# ONOFRE_ESTORES_COVERS_R1_1.net
KiCad netlist of a schematic drawn in EAGLE
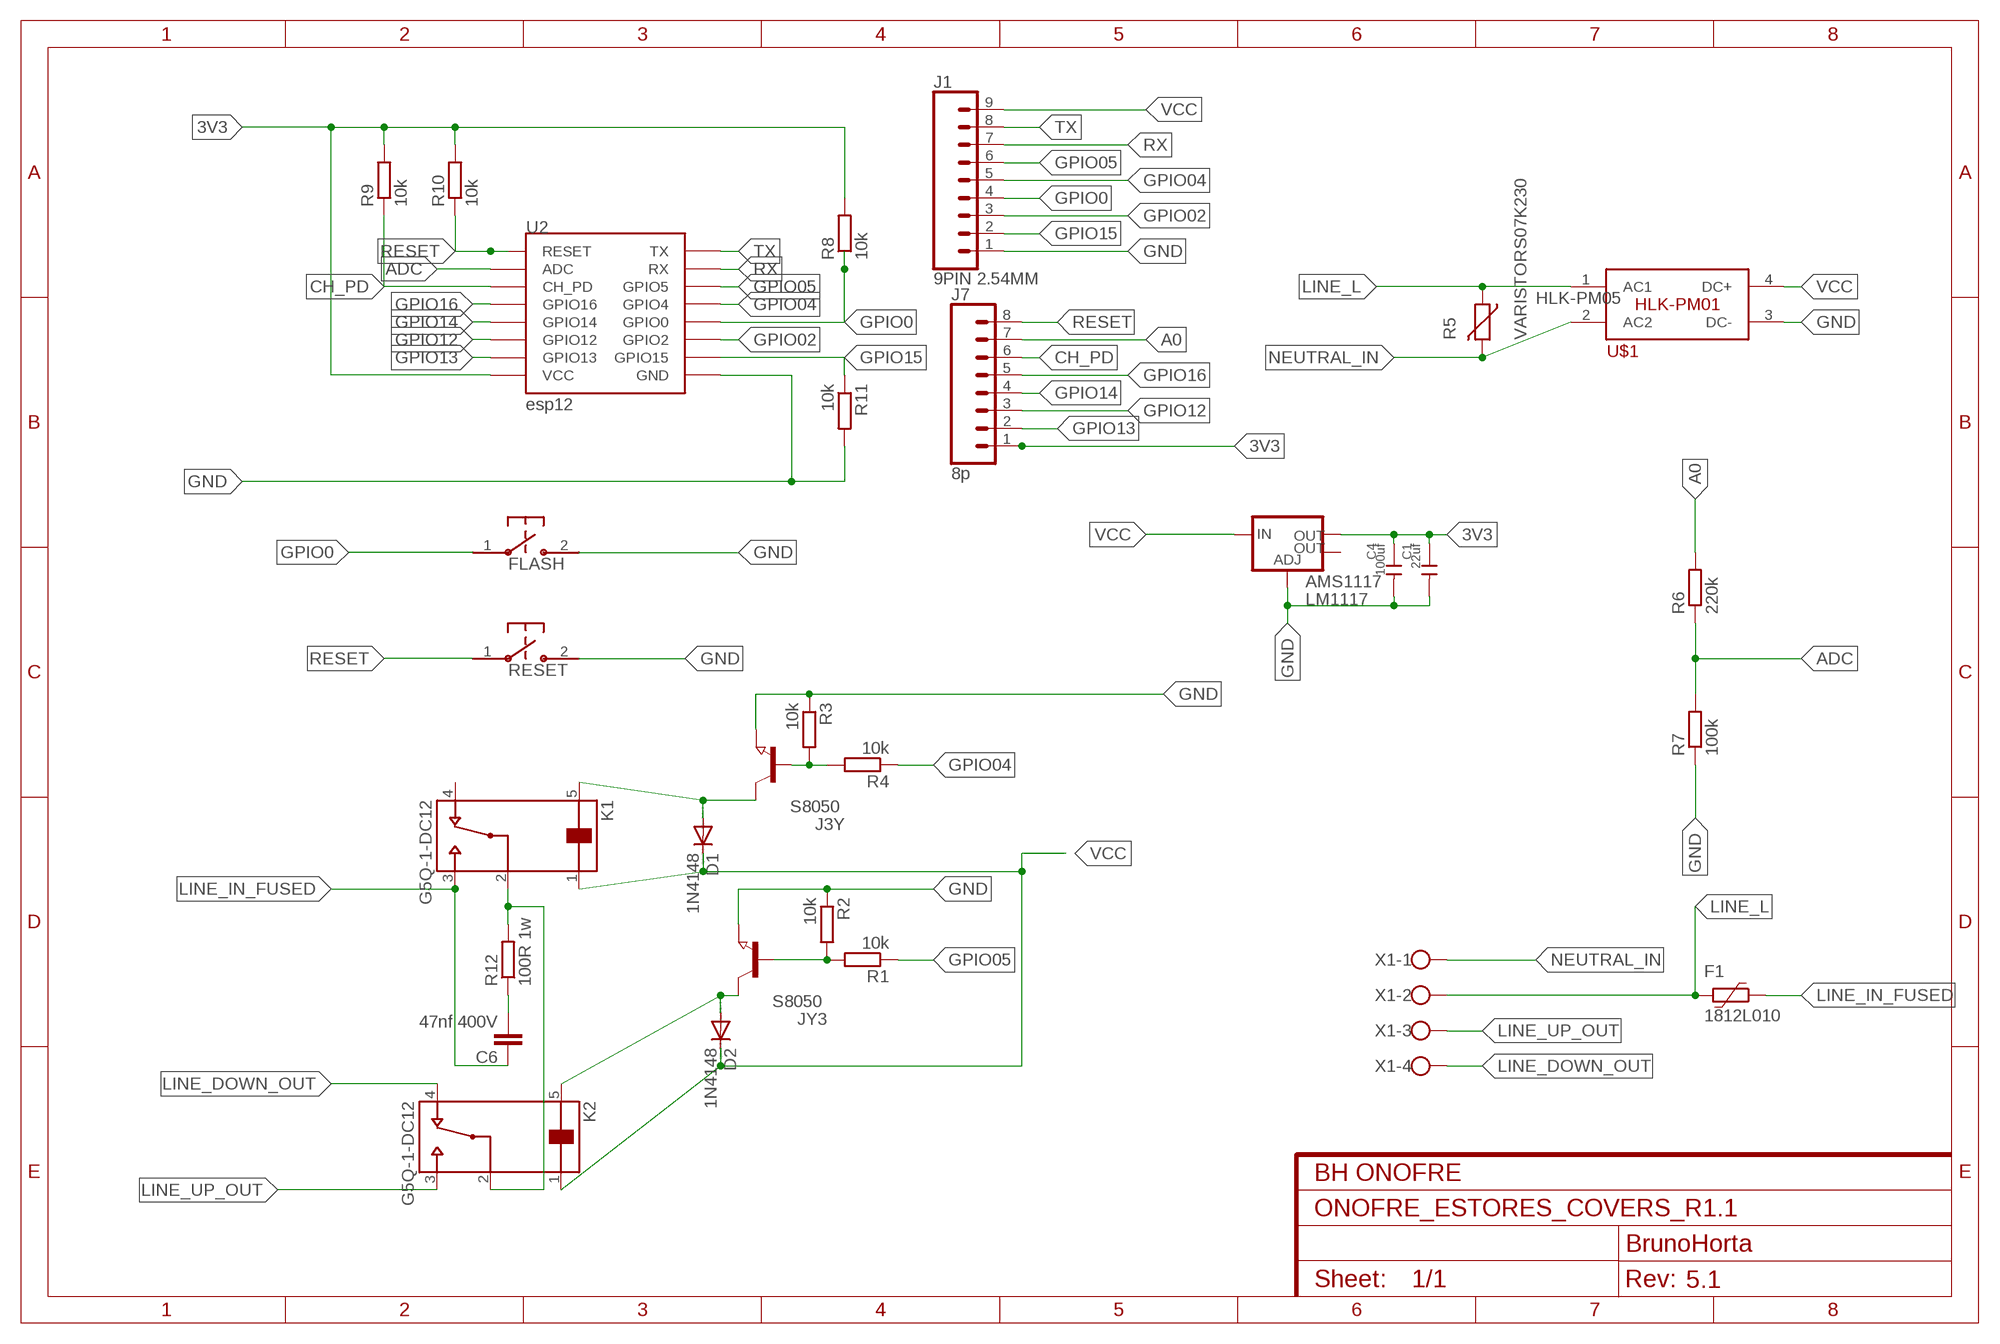
[diagram p0: schematic, sheet 1]

(export (version "E")
  (design (tool "Eeschema 10.0.6"))
  (components
    (comp (ref "AMS1117")
      (value "LM1117")
      (footprint "eagle-import:SOT223")
      (libsource (lib "eagle-import") (part "V_REG_LM1117SOT223"))
    )
    (comp (ref "C1")
      (value "22uf")
      (footprint "eagle-import:C1206")
      (fields (field (name "MPN") "CC1206KKX7RCBB102"))
      (libsource (lib "eagle-import") (part "CERAMIC-1NF-1KV-10%-X7R?(1206)"))
    )
    (comp (ref "C4")
      (value "100uf")
      (footprint "eagle-import:C1206")
      (fields (field (name "MPN") "CC1206KKX7RCBB102"))
      (libsource (lib "eagle-import") (part "CERAMIC-1NF-1KV-10%-X7R?(1206)"))
    )
    (comp (ref "C6")
      (value "47nf 400V")
      (footprint "eagle-import:C102-043X133")
      (libsource (lib "eagle-import") (part "C-EU102-043X133"))
    )
    (comp (ref "D1")
      (value "1N4148")
      (footprint "eagle-import:SOD80C")
      (libsource (lib "eagle-import") (part "DIODE-SOD80C"))
    )
    (comp (ref "D2")
      (value "1N4148")
      (footprint "eagle-import:SOD80C")
      (libsource (lib "eagle-import") (part "DIODE-SOD80C"))
    )
    (comp (ref "F1")
      (value "1812L010")
      (footprint "eagle-import:1812L")
      (fields (field (name "MF") "Littelfuse"))
      (libsource (lib "eagle-import") (part "?1812L010"))
    )
    (comp (ref "FLASH")
      (value "B3U-1000P-2P-SMD")
      (footprint "eagle-import:B3U-1000P")
      (fields (field (name "MANUFACTURER") "Omron") (field (name "MPN") "B3U-1000P"))
      (libsource (lib "eagle-import") (part "B3U-1000P"))
    )
    (comp (ref "J1")
      (value "9PIN 2.54MM")
      (footprint "eagle-import:1X09")
      (libsource (lib "eagle-import") (part "CONN_09"))
    )
    (comp (ref "J3Y")
      (value "S8050")
      (footprint "eagle-import:SOT23")
      (libsource (lib "eagle-import") (part "NPN-TRANSISTOR_SOT23"))
    )
    (comp (ref "J7")
      (value "8p")
      (footprint "eagle-import:1X08")
      (libsource (lib "eagle-import") (part "CONN_08{dblquote}"))
    )
    (comp (ref "JY3")
      (value "S8050")
      (footprint "eagle-import:SOT23")
      (libsource (lib "eagle-import") (part "NPN-TRANSISTOR_SOT23"))
    )
    (comp (ref "K1")
      (value "G5Q-1-DC12")
      (footprint "eagle-import:RELAY_G5Q-1-DC12")
      (fields (field (name "MF") "Omron"))
      (libsource (lib "eagle-import") (part "G5Q-1-DC12"))
    )
    (comp (ref "K2")
      (value "G5Q-1-DC12")
      (footprint "eagle-import:RELAY_G5Q-1-DC12")
      (fields (field (name "MF") "Omron"))
      (libsource (lib "eagle-import") (part "G5Q-1-DC12"))
    )
    (comp (ref "R1")
      (value "10k")
      (footprint "eagle-import:R0603")
      (libsource (lib "eagle-import") (part "R-EU_R0603"))
    )
    (comp (ref "R2")
      (value "10k")
      (footprint "eagle-import:R0603")
      (libsource (lib "eagle-import") (part "R-EU_R0603"))
    )
    (comp (ref "R3")
      (value "10k")
      (footprint "eagle-import:R0603")
      (libsource (lib "eagle-import") (part "R-EU_R0603"))
    )
    (comp (ref "R4")
      (value "10k")
      (footprint "eagle-import:R0603")
      (libsource (lib "eagle-import") (part "R-EU_R0603"))
    )
    (comp (ref "R5")
      (value "VARISTORS07K230")
      (footprint "eagle-import:S07K230")
      (libsource (lib "eagle-import") (part "VARISTORS07K230"))
    )
    (comp (ref "R6")
      (value "220k")
      (footprint "eagle-import:R0603")
      (libsource (lib "eagle-import") (part "R-EU_R0603"))
    )
    (comp (ref "R7")
      (value "100k")
      (footprint "eagle-import:R0603")
      (libsource (lib "eagle-import") (part "R-EU_R0603"))
    )
    (comp (ref "R8")
      (value "10k")
      (footprint "eagle-import:R0603")
      (libsource (lib "eagle-import") (part "R-EU_R0603"))
    )
    (comp (ref "R9")
      (value "10k")
      (footprint "eagle-import:R0603")
      (libsource (lib "eagle-import") (part "R-EU_R0603"))
    )
    (comp (ref "R10")
      (value "10k")
      (footprint "eagle-import:R0603")
      (libsource (lib "eagle-import") (part "R-EU_R0603"))
    )
    (comp (ref "R11")
      (value "10k")
      (footprint "eagle-import:R0603")
      (libsource (lib "eagle-import") (part "R-EU_R0603"))
    )
    (comp (ref "R12")
      (value "100R 1w")
      (footprint "eagle-import:R2512")
      (libsource (lib "eagle-import") (part "R-EU_R2512"))
    )
    (comp (ref "RESET")
      (value "B3U-1000P-2P-SMD")
      (footprint "eagle-import:B3U-1000P")
      (fields (field (name "MANUFACTURER") "Omron") (field (name "MPN") "B3U-1000P"))
      (libsource (lib "eagle-import") (part "B3U-1000P"))
    )
    (comp (ref "U$1")
      (value "HLK-PM01")
      (footprint "eagle-import:HLK-PM01")
      (fields (field (name "MF") "Hi-link") (field (name "MP") "hlk-pm01"))
      (libsource (lib "eagle-import") (part "HLK-PM01"))
    )
    (comp (ref "U2")
      (value "esp12")
      (footprint "eagle-import:ESP12-SMD")
      (libsource (lib "eagle-import") (part "ESP12SMD"))
    )
    (comp (ref "X1")
      (value "W237-4")
      (footprint "eagle-import:W237-4")
      (libsource (lib "eagle-import") (part "W237-4"))
    )
  )
  (nets
    (net (code "1") (name "3V3") (class "Default")
      (node (ref "AMS1117") (pin "2") (pinfunction "OUT_2") (pintype "output"))
      (node (ref "C1") (pin "1") (pinfunction "1_1") (pintype "passive"))
      (node (ref "C4") (pin "1") (pinfunction "1_1") (pintype "passive"))
      (node (ref "J7") (pin "1") (pinfunction "1_1") (pintype "passive"))
      (node (ref "R10") (pin "2") (pinfunction "2_2") (pintype "passive"))
      (node (ref "R8") (pin "2") (pinfunction "2_2") (pintype "passive"))
      (node (ref "R9") (pin "2") (pinfunction "2_2") (pintype "passive"))
      (node (ref "U2") (pin "VCC") (pinfunction "VCC_VCC") (pintype "bidirectional"))
    )
    (net (code "2") (name "A0") (class "Default")
      (node (ref "J7") (pin "7") (pinfunction "7_7") (pintype "passive"))
      (node (ref "R6") (pin "2") (pinfunction "2_2") (pintype "passive"))
    )
    (net (code "3") (name "ADC") (class "Default")
      (node (ref "R6") (pin "1") (pinfunction "1_1") (pintype "passive"))
      (node (ref "R7") (pin "2") (pinfunction "2_2") (pintype "passive"))
      (node (ref "U2") (pin "ADC") (pinfunction "ADC_ADC") (pintype "bidirectional"))
    )
    (net (code "4") (name "CH_PD") (class "Default")
      (node (ref "J7") (pin "6") (pinfunction "6_6") (pintype "passive"))
      (node (ref "R9") (pin "1") (pinfunction "1_1") (pintype "passive"))
      (node (ref "U2") (pin "CH_PD") (pinfunction "CH_PD_CH_PD") (pintype "bidirectional"))
    )
    (net (code "5") (name "GND") (class "Default")
      (node (ref "AMS1117") (pin "1") (pinfunction "ADJ_1") (pintype "input"))
      (node (ref "C1") (pin "2") (pinfunction "2_2") (pintype "passive"))
      (node (ref "C4") (pin "2") (pinfunction "2_2") (pintype "passive"))
      (node (ref "FLASH") (pin "2") (pinfunction "P$2_2") (pintype "passive"))
      (node (ref "J1") (pin "1") (pinfunction "1_1") (pintype "passive"))
      (node (ref "J3Y") (pin "2") (pinfunction "E_2") (pintype "passive"))
      (node (ref "JY3") (pin "2") (pinfunction "E_2") (pintype "passive"))
      (node (ref "R11") (pin "2") (pinfunction "2_2") (pintype "passive"))
      (node (ref "R2") (pin "1") (pinfunction "1_1") (pintype "passive"))
      (node (ref "R3") (pin "1") (pinfunction "1_1") (pintype "passive"))
      (node (ref "R7") (pin "1") (pinfunction "1_1") (pintype "passive"))
      (node (ref "RESET") (pin "2") (pinfunction "P$2_2") (pintype "passive"))
      (node (ref "U$1") (pin "3") (pinfunction "DC-_3") (pintype "power_in"))
      (node (ref "U2") (pin "GND") (pinfunction "GND_GND") (pintype "bidirectional"))
    )
    (net (code "6") (name "GPIO0") (class "Default")
      (node (ref "FLASH") (pin "1") (pinfunction "P$1_1") (pintype "passive"))
      (node (ref "J1") (pin "4") (pinfunction "4_4") (pintype "passive"))
      (node (ref "R8") (pin "1") (pinfunction "1_1") (pintype "passive"))
      (node (ref "U2") (pin "GPIO0") (pinfunction "GPIO0_GPIO0") (pintype "bidirectional"))
    )
    (net (code "7") (name "GPIO02") (class "Default")
      (node (ref "J1") (pin "3") (pinfunction "3_3") (pintype "passive"))
      (node (ref "U2") (pin "GPIO2") (pinfunction "GPIO2_GPIO2") (pintype "bidirectional"))
    )
    (net (code "8") (name "GPIO04") (class "Default")
      (node (ref "J1") (pin "5") (pinfunction "5_5") (pintype "passive"))
      (node (ref "R4") (pin "1") (pinfunction "1_1") (pintype "passive"))
      (node (ref "U2") (pin "GPIO4") (pinfunction "GPIO4_GPIO4") (pintype "bidirectional"))
    )
    (net (code "9") (name "GPIO05") (class "Default")
      (node (ref "J1") (pin "6") (pinfunction "6_6") (pintype "passive"))
      (node (ref "R1") (pin "1") (pinfunction "1_1") (pintype "passive"))
      (node (ref "U2") (pin "GPIO5") (pinfunction "GPIO5_GPIO5") (pintype "bidirectional"))
    )
    (net (code "10") (name "GPIO12") (class "Default")
      (node (ref "J7") (pin "3") (pinfunction "3_3") (pintype "passive"))
      (node (ref "U2") (pin "GPIO12") (pinfunction "GPIO12_GPIO12") (pintype "bidirectional"))
    )
    (net (code "11") (name "GPIO13") (class "Default")
      (node (ref "J7") (pin "2") (pinfunction "2_2") (pintype "passive"))
      (node (ref "U2") (pin "GPIO13") (pinfunction "GPIO13_GPIO13") (pintype "bidirectional"))
    )
    (net (code "12") (name "GPIO14") (class "Default")
      (node (ref "J7") (pin "4") (pinfunction "4_4") (pintype "passive"))
      (node (ref "U2") (pin "GPIO14") (pinfunction "GPIO14_GPIO14") (pintype "bidirectional"))
    )
    (net (code "13") (name "GPIO15") (class "Default")
      (node (ref "J1") (pin "2") (pinfunction "2_2") (pintype "passive"))
      (node (ref "R11") (pin "1") (pinfunction "1_1") (pintype "passive"))
      (node (ref "U2") (pin "GPIO15") (pinfunction "GPIO15_GPIO15") (pintype "bidirectional"))
    )
    (net (code "14") (name "GPIO16") (class "Default")
      (node (ref "J7") (pin "5") (pinfunction "5_5") (pintype "passive"))
      (node (ref "U2") (pin "GPIO16") (pinfunction "GPIO16_GPIO16") (pintype "bidirectional"))
    )
    (net (code "15") (name "LINE_DOWN_OUT") (class "Default")
      (node (ref "K2") (pin "4") (pinfunction "4_4") (pintype "passive"))
      (node (ref "X1") (pin "4") (pinfunction "KL_4") (pintype "passive"))
    )
    (net (code "16") (name "LINE_IN_FUSED") (class "Default")
      (node (ref "C6") (pin "1") (pinfunction "1_1") (pintype "passive"))
      (node (ref "F1") (pin "1") (pinfunction "1_1") (pintype "passive"))
      (node (ref "K1") (pin "3") (pinfunction "3_3") (pintype "passive"))
    )
    (net (code "17") (name "LINE_L") (class "Default")
      (node (ref "F1") (pin "2") (pinfunction "2_2") (pintype "passive"))
      (node (ref "R5") (pin "1") (pinfunction "1_1") (pintype "passive"))
      (node (ref "U$1") (pin "1") (pinfunction "AC1_1") (pintype "power_in"))
      (node (ref "X1") (pin "2") (pinfunction "KL_2") (pintype "passive"))
    )
    (net (code "18") (name "LINE_UP_OUT") (class "Default")
      (node (ref "K2") (pin "3") (pinfunction "3_3") (pintype "passive"))
      (node (ref "X1") (pin "3") (pinfunction "KL_3") (pintype "passive"))
    )
    (net (code "19") (name "NEUTRAL_IN") (class "Default")
      (node (ref "R5") (pin "2") (pinfunction "2_2") (pintype "passive"))
      (node (ref "U$1") (pin "2") (pinfunction "AC2_2") (pintype "power_in"))
      (node (ref "X1") (pin "1") (pinfunction "KL_1") (pintype "passive"))
    )
    (net (code "20") (name "Net-(C6-Pad2)") (class "Default")
      (node (ref "C6") (pin "2") (pinfunction "2_2") (pintype "passive"))
      (node (ref "R12") (pin "1") (pinfunction "1_1") (pintype "passive"))
    )
    (net (code "21") (name "Net-(J3Y-B)") (class "Default")
      (node (ref "J3Y") (pin "1") (pinfunction "B_1") (pintype "passive"))
      (node (ref "R3") (pin "2") (pinfunction "2_2") (pintype "passive"))
      (node (ref "R4") (pin "2") (pinfunction "2_2") (pintype "passive"))
    )
    (net (code "22") (name "Net-(J3Y-C)") (class "Default")
      (node (ref "D1") (pin "A") (pinfunction "A_A") (pintype "passive"))
      (node (ref "J3Y") (pin "3") (pinfunction "C_3") (pintype "passive"))
      (node (ref "K1") (pin "5") (pinfunction "5_5") (pintype "passive"))
    )
    (net (code "23") (name "Net-(JY3-B)") (class "Default")
      (node (ref "JY3") (pin "1") (pinfunction "B_1") (pintype "passive"))
      (node (ref "R1") (pin "2") (pinfunction "2_2") (pintype "passive"))
      (node (ref "R2") (pin "2") (pinfunction "2_2") (pintype "passive"))
    )
    (net (code "24") (name "Net-(JY3-C)") (class "Default")
      (node (ref "D2") (pin "A") (pinfunction "A_A") (pintype "passive"))
      (node (ref "JY3") (pin "3") (pinfunction "C_3") (pintype "passive"))
      (node (ref "K2") (pin "5") (pinfunction "5_5") (pintype "passive"))
    )
    (net (code "25") (name "Net-(K1-Pad2)") (class "Default")
      (node (ref "K1") (pin "2") (pinfunction "2_2") (pintype "passive"))
      (node (ref "K2") (pin "2") (pinfunction "2_2") (pintype "passive"))
      (node (ref "R12") (pin "2") (pinfunction "2_2") (pintype "passive"))
    )
    (net (code "26") (name "RESET") (class "Default")
      (node (ref "J7") (pin "8") (pinfunction "8_8") (pintype "passive"))
      (node (ref "R10") (pin "1") (pinfunction "1_1") (pintype "passive"))
      (node (ref "RESET") (pin "1") (pinfunction "P$1_1") (pintype "passive"))
      (node (ref "U2") (pin "RESET") (pinfunction "RESET_RESET") (pintype "bidirectional"))
    )
    (net (code "27") (name "RX") (class "Default")
      (node (ref "J1") (pin "7") (pinfunction "7_7") (pintype "passive"))
      (node (ref "U2") (pin "RXD0") (pinfunction "RX_RXD0") (pintype "bidirectional"))
    )
    (net (code "28") (name "TX") (class "Default")
      (node (ref "J1") (pin "8") (pinfunction "8_8") (pintype "passive"))
      (node (ref "U2") (pin "TXD0") (pinfunction "TX_TXD0") (pintype "bidirectional"))
    )
    (net (code "29") (name "VCC") (class "Default")
      (node (ref "AMS1117") (pin "3") (pinfunction "IN_3") (pintype "input"))
      (node (ref "D1") (pin "C") (pinfunction "C_C") (pintype "passive"))
      (node (ref "D2") (pin "C") (pinfunction "C_C") (pintype "passive"))
      (node (ref "J1") (pin "9") (pinfunction "9_9") (pintype "passive"))
      (node (ref "K1") (pin "1") (pinfunction "1_1") (pintype "passive"))
      (node (ref "K2") (pin "1") (pinfunction "1_1") (pintype "passive"))
      (node (ref "U$1") (pin "4") (pinfunction "DC+_4") (pintype "power_in"))
    )
    (net (code "30") (name "unconnected-(AMS1117-OUT-Pad4)") (class "Default")
      (node (ref "AMS1117") (pin "4") (pinfunction "OUT_4") (pintype "output"))
    )
    (net (code "31") (name "unconnected-(K1-Pad4)") (class "Default")
      (node (ref "K1") (pin "4") (pinfunction "4_4") (pintype "passive"))
    )
  )
)
